# sinclair_keyboard_cable_flip_v2_5.net
KiCad netlist of a schematic drawn in EAGLE
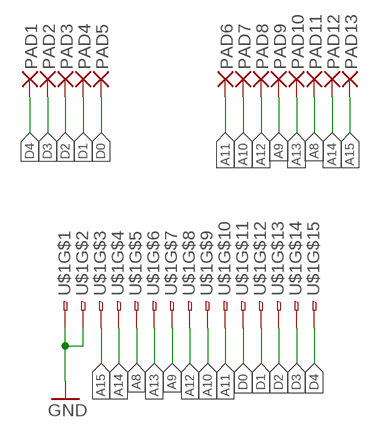
[diagram p0: schematic, sheet 1]

(export (version "E")
  (design (tool "Eeschema 10.0.6"))
  (components
    (comp (ref "PAD1")
      (value "SMD230MIL")
      (footprint "eagle-import:SMD1,27-762")
      (libsource (lib "eagle-import") (part "SMD230MIL"))
    )
    (comp (ref "PAD2")
      (value "SMD230MIL")
      (footprint "eagle-import:SMD1,27-762")
      (libsource (lib "eagle-import") (part "SMD230MIL"))
    )
    (comp (ref "PAD3")
      (value "SMD230MIL")
      (footprint "eagle-import:SMD1,27-762")
      (libsource (lib "eagle-import") (part "SMD230MIL"))
    )
    (comp (ref "PAD4")
      (value "SMD230MIL")
      (footprint "eagle-import:SMD1,27-762")
      (libsource (lib "eagle-import") (part "SMD230MIL"))
    )
    (comp (ref "PAD5")
      (value "SMD230MIL")
      (footprint "eagle-import:SMD1,27-762")
      (libsource (lib "eagle-import") (part "SMD230MIL"))
    )
    (comp (ref "PAD6")
      (value "SMD230MIL")
      (footprint "eagle-import:SMD1,27-762")
      (libsource (lib "eagle-import") (part "SMD230MIL"))
    )
    (comp (ref "PAD7")
      (value "SMD230MIL")
      (footprint "eagle-import:SMD1,27-762")
      (libsource (lib "eagle-import") (part "SMD230MIL"))
    )
    (comp (ref "PAD8")
      (value "SMD230MIL")
      (footprint "eagle-import:SMD1,27-762")
      (libsource (lib "eagle-import") (part "SMD230MIL"))
    )
    (comp (ref "PAD9")
      (value "SMD230MIL")
      (footprint "eagle-import:SMD1,27-762")
      (libsource (lib "eagle-import") (part "SMD230MIL"))
    )
    (comp (ref "PAD10")
      (value "SMD230MIL")
      (footprint "eagle-import:SMD1,27-762")
      (libsource (lib "eagle-import") (part "SMD230MIL"))
    )
    (comp (ref "PAD11")
      (value "SMD230MIL")
      (footprint "eagle-import:SMD1,27-762")
      (libsource (lib "eagle-import") (part "SMD230MIL"))
    )
    (comp (ref "PAD12")
      (value "SMD230MIL")
      (footprint "eagle-import:SMD1,27-762")
      (libsource (lib "eagle-import") (part "SMD230MIL"))
    )
    (comp (ref "PAD13")
      (value "SMD230MIL")
      (footprint "eagle-import:SMD1,27-762")
      (libsource (lib "eagle-import") (part "SMD230MIL"))
    )
    (comp (ref "U$1")
      (value "FH12-15S-1SHFFC")
      (footprint "eagle-import:FFC-15")
      (libsource (lib "eagle-import") (part "FH12-15S-1SHFFC"))
    )
  )
  (nets
    (net (code "1") (name "A8") (class "Default")
      (node (ref "PAD11") (pin "1") (pinfunction "P_1") (pintype "passive"))
      (node (ref "U$1") (pin "5") (pinfunction "1_5") (pintype "passive"))
    )
    (net (code "2") (name "A9") (class "Default")
      (node (ref "PAD9") (pin "1") (pinfunction "P_1") (pintype "passive"))
      (node (ref "U$1") (pin "7") (pinfunction "1_7") (pintype "passive"))
    )
    (net (code "3") (name "A10") (class "Default")
      (node (ref "PAD7") (pin "1") (pinfunction "P_1") (pintype "passive"))
      (node (ref "U$1") (pin "9") (pinfunction "1_9") (pintype "passive"))
    )
    (net (code "4") (name "A11") (class "Default")
      (node (ref "PAD6") (pin "1") (pinfunction "P_1") (pintype "passive"))
      (node (ref "U$1") (pin "10") (pinfunction "1_10") (pintype "passive"))
    )
    (net (code "5") (name "A12") (class "Default")
      (node (ref "PAD8") (pin "1") (pinfunction "P_1") (pintype "passive"))
      (node (ref "U$1") (pin "8") (pinfunction "1_8") (pintype "passive"))
    )
    (net (code "6") (name "A13") (class "Default")
      (node (ref "PAD10") (pin "1") (pinfunction "P_1") (pintype "passive"))
      (node (ref "U$1") (pin "6") (pinfunction "1_6") (pintype "passive"))
    )
    (net (code "7") (name "A14") (class "Default")
      (node (ref "PAD12") (pin "1") (pinfunction "P_1") (pintype "passive"))
      (node (ref "U$1") (pin "4") (pinfunction "1_4") (pintype "passive"))
    )
    (net (code "8") (name "A15") (class "Default")
      (node (ref "PAD13") (pin "1") (pinfunction "P_1") (pintype "passive"))
      (node (ref "U$1") (pin "3") (pinfunction "1_3") (pintype "passive"))
    )
    (net (code "9") (name "D0") (class "Default")
      (node (ref "PAD5") (pin "1") (pinfunction "P_1") (pintype "passive"))
      (node (ref "U$1") (pin "11") (pinfunction "1_11") (pintype "passive"))
    )
    (net (code "10") (name "D1") (class "Default")
      (node (ref "PAD4") (pin "1") (pinfunction "P_1") (pintype "passive"))
      (node (ref "U$1") (pin "12") (pinfunction "1_12") (pintype "passive"))
    )
    (net (code "11") (name "D2") (class "Default")
      (node (ref "PAD3") (pin "1") (pinfunction "P_1") (pintype "passive"))
      (node (ref "U$1") (pin "13") (pinfunction "1_13") (pintype "passive"))
    )
    (net (code "12") (name "D3") (class "Default")
      (node (ref "PAD2") (pin "1") (pinfunction "P_1") (pintype "passive"))
      (node (ref "U$1") (pin "14") (pinfunction "1_14") (pintype "passive"))
    )
    (net (code "13") (name "D4") (class "Default")
      (node (ref "PAD1") (pin "1") (pinfunction "P_1") (pintype "passive"))
      (node (ref "U$1") (pin "15") (pinfunction "1_15") (pintype "passive"))
    )
    (net (code "14") (name "GND") (class "Default")
      (node (ref "U$1") (pin "1") (pinfunction "1_1") (pintype "passive"))
      (node (ref "U$1") (pin "2") (pinfunction "1_2") (pintype "passive"))
    )
  )
)
